# InterfacesA_CONNECTORS.net
KiCad netlist of a schematic drawn in Altium Designer
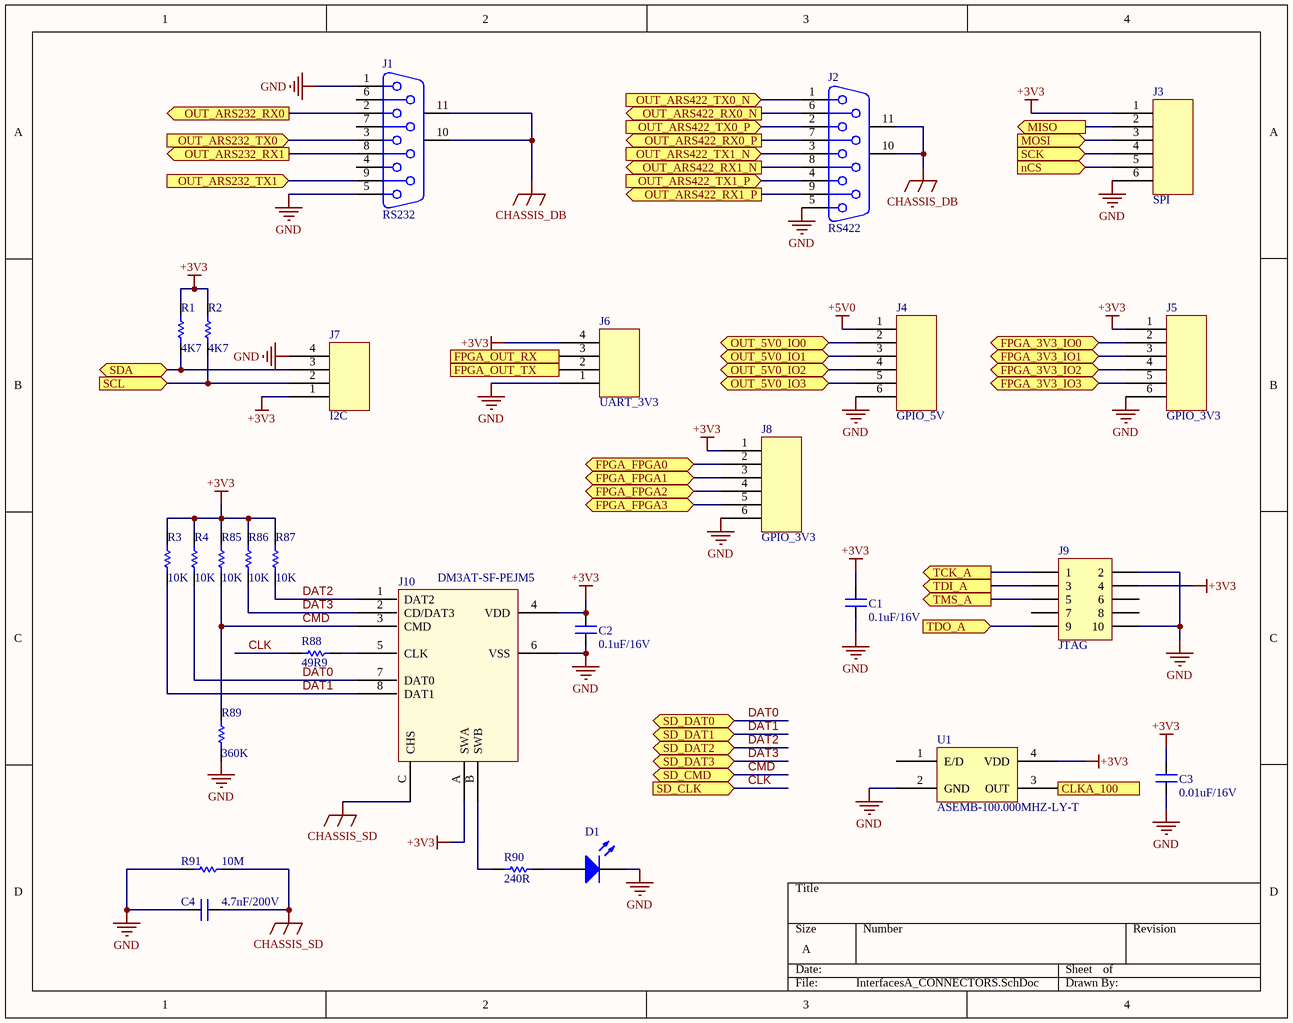
[diagram p0: InterfacesA_CONNECTORS.SchDoc]

(export (version "E")
  (design (tool "Eeschema 10.0.6"))
  (components
    (comp (ref "C1")
      (value "0.1uF/16V")
      (footprint "CAP_0805")
      (fields (field (name "Comment") "CAP_0805"))
      (libsource (lib "AdapterLib") (part "CAP_0805"))
    )
    (comp (ref "C2")
      (value "0.1uF/16V")
      (footprint "CAP_0805")
      (fields (field (name "Comment") "CAP_0805"))
      (libsource (lib "AdapterLib") (part "CAP_0805"))
    )
    (comp (ref "C3")
      (value "0.01uF/16V")
      (footprint "CAP_0805")
      (fields (field (name "Comment") "CAP_0805"))
      (libsource (lib "AdapterLib") (part "CAP_0805"))
    )
    (comp (ref "C4")
      (value "4.7nF/200V")
      (footprint "CAP_0805")
      (fields (field (name "Comment") "CAP_0805"))
      (libsource (lib "AdapterLib") (part "CAP_0805"))
    )
    (comp (ref "D1")
      (value "LED_0603")
      (footprint "LED_0603")
      (libsource (lib "AdapterLib") (part "LED_0603"))
    )
    (comp (ref "J1")
      (value "RS232")
      (footprint "D09S33E4GV00LF")
      (libsource (lib "AdapterLib") (part "D09S33E4GV00LF"))
    )
    (comp (ref "J2")
      (value "RS422")
      (footprint "D09S33E4GV00LF")
      (libsource (lib "AdapterLib") (part "D09S33E4GV00LF"))
    )
    (comp (ref "J3") (value "SPI") (footprint "HEADER_6") (libsource (lib "AdapterLib") (part "HEADER_6")))
    (comp (ref "J4")
      (value "GPIO_5V")
      (footprint "HEADER_6")
      (libsource (lib "AdapterLib") (part "HEADER_6"))
    )
    (comp (ref "J5")
      (value "GPIO_3V3")
      (footprint "HEADER_6")
      (libsource (lib "AdapterLib") (part "HEADER_6"))
    )
    (comp (ref "J6")
      (value "UART_3V3")
      (footprint "HEADER_4")
      (libsource (lib "AdapterLib") (part "HEADER_4"))
    )
    (comp (ref "J7") (value "I2C") (footprint "HEADER_4") (libsource (lib "AdapterLib") (part "HEADER_4")))
    (comp (ref "J8")
      (value "GPIO_3V3")
      (footprint "HEADER_6")
      (libsource (lib "AdapterLib") (part "HEADER_6"))
    )
    (comp (ref "J9")
      (value "JTAG")
      (footprint "HEADER 5x2")
      (description "Header, 5-Pin, Dual row")
      (fields (field (name "PUBLISHER") "Altium Limited"))
      (libsource (lib "AdapterLib") (part "Header 5X2"))
    )
    (comp (ref "J10")
      (value "DM3AT-SF-PEJM5")
      (footprint "DM3AT-SF-PEJM5")
      (description "CONN SM MicroSD")
      (libsource (lib "AdapterLib") (part "DM3AT-SF-PEJM5"))
    )
    (comp (ref "R1")
      (value "4K7")
      (footprint "RES_0805")
      (fields (field (name "Comment") "RES_0805"))
      (libsource (lib "AdapterLib") (part "RES_0805"))
    )
    (comp (ref "R2")
      (value "4K7")
      (footprint "RES_0805")
      (fields (field (name "Comment") "RES_0805"))
      (libsource (lib "AdapterLib") (part "RES_0805"))
    )
    (comp (ref "R3")
      (value "10K")
      (footprint "RES_0805")
      (fields (field (name "Comment") "RES_0805"))
      (libsource (lib "AdapterLib") (part "RES_0805"))
    )
    (comp (ref "R4")
      (value "10K")
      (footprint "RES_0805")
      (fields (field (name "Comment") "RES_0805"))
      (libsource (lib "AdapterLib") (part "RES_0805"))
    )
    (comp (ref "R85")
      (value "10K")
      (footprint "RES_0805")
      (fields (field (name "Comment") "RES_0805"))
      (libsource (lib "AdapterLib") (part "RES_0805"))
    )
    (comp (ref "R86")
      (value "10K")
      (footprint "RES_0805")
      (fields (field (name "Comment") "RES_0805"))
      (libsource (lib "AdapterLib") (part "RES_0805"))
    )
    (comp (ref "R87")
      (value "10K")
      (footprint "RES_0805")
      (fields (field (name "Comment") "RES_0805"))
      (libsource (lib "AdapterLib") (part "RES_0805"))
    )
    (comp (ref "R88")
      (value "49R9")
      (footprint "RES_0805")
      (fields (field (name "Comment") "RES_0805"))
      (libsource (lib "AdapterLib") (part "RES_0805"))
    )
    (comp (ref "R89")
      (value "360K")
      (footprint "RES_0805")
      (fields (field (name "Comment") "RES_0805"))
      (libsource (lib "AdapterLib") (part "RES_0805"))
    )
    (comp (ref "R90")
      (value "240R")
      (footprint "RES_0805")
      (fields (field (name "Comment") "RES_0805"))
      (libsource (lib "AdapterLib") (part "RES_0805"))
    )
    (comp (ref "R91")
      (value "10M")
      (footprint "RES_0805")
      (fields (field (name "Comment") "RES_0805"))
      (libsource (lib "AdapterLib") (part "RES_0805"))
    )
    (comp (ref "U1")
      (value "ASEMB-100.000MHZ-LY-T")
      (footprint "ASEMB-100.000MHZ-LY-T")
      (libsource (lib "AdapterLib") (part "ASEMB-100.000MHZ-LY-T"))
    )
  )
  (nets
    (net (code "1") (name "+3V3") (class "Default")
      (node (ref "C1") (pin "2") (pinfunction "2_2") (pintype "passive"))
      (node (ref "C2") (pin "2") (pinfunction "2_2") (pintype "passive"))
      (node (ref "C3") (pin "2") (pinfunction "2_2") (pintype "passive"))
      (node (ref "J10") (pin "4") (pinfunction "VDD_4") (pintype "passive"))
      (node (ref "J10") (pin "A") (pinfunction "SWA_A") (pintype "passive"))
      (node (ref "J3") (pin "1") (pintype "passive"))
      (node (ref "J5") (pin "1") (pintype "passive"))
      (node (ref "J6") (pin "4") (pintype "passive"))
      (node (ref "J7") (pin "1") (pintype "passive"))
      (node (ref "J8") (pin "1") (pintype "passive"))
      (node (ref "J9") (pin "4") (pinfunction "4_4") (pintype "passive"))
      (node (ref "R1") (pin "2") (pinfunction "2_2") (pintype "passive"))
      (node (ref "R2") (pin "2") (pinfunction "2_2") (pintype "passive"))
      (node (ref "R3") (pin "2") (pinfunction "2_2") (pintype "passive"))
      (node (ref "R4") (pin "2") (pinfunction "2_2") (pintype "passive"))
      (node (ref "R85") (pin "2") (pinfunction "2_2") (pintype "passive"))
      (node (ref "R86") (pin "2") (pinfunction "2_2") (pintype "passive"))
      (node (ref "R87") (pin "2") (pinfunction "2_2") (pintype "passive"))
      (node (ref "U1") (pin "4") (pinfunction "VDD_4") (pintype "passive"))
    )
    (net (code "2") (name "+5V0") (class "Default") (node (ref "J4") (pin "1") (pintype "passive")))
    (net (code "3") (name "/CLK") (class "Default")
      (node (ref "R88") (pin "2") (pinfunction "2_2") (pintype "passive"))
    )
    (net (code "4") (name "/CLKA_100") (class "Default")
      (node (ref "U1") (pin "3") (pinfunction "OUT_3") (pintype "passive"))
    )
    (net (code "5") (name "/CMD") (class "Default")
      (node (ref "J10") (pin "3") (pinfunction "CMD_3") (pintype "passive"))
      (node (ref "R85") (pin "1") (pinfunction "1_1") (pintype "passive"))
      (node (ref "R89") (pin "2") (pinfunction "2_2") (pintype "passive"))
    )
    (net (code "6") (name "/DAT0") (class "Default")
      (node (ref "J10") (pin "7") (pinfunction "DAT0_7") (pintype "passive"))
      (node (ref "R4") (pin "1") (pinfunction "1_1") (pintype "passive"))
    )
    (net (code "7") (name "/DAT1") (class "Default")
      (node (ref "J10") (pin "8") (pinfunction "DAT1_8") (pintype "passive"))
      (node (ref "R3") (pin "1") (pinfunction "1_1") (pintype "passive"))
    )
    (net (code "8") (name "/DAT2") (class "Default")
      (node (ref "J10") (pin "1") (pinfunction "DAT2_1") (pintype "passive"))
      (node (ref "R87") (pin "1") (pinfunction "1_1") (pintype "passive"))
    )
    (net (code "9") (name "/DAT3") (class "Default")
      (node (ref "J10") (pin "2") (pinfunction "CD/DAT3_2") (pintype "passive"))
      (node (ref "R86") (pin "1") (pinfunction "1_1") (pintype "passive"))
    )
    (net (code "10") (name "/FPGA_3V3_IO0") (class "Default") (node (ref "J5") (pin "2") (pintype "passive")))
    (net (code "11") (name "/FPGA_3V3_IO1") (class "Default") (node (ref "J5") (pin "3") (pintype "passive")))
    (net (code "12") (name "/FPGA_3V3_IO2") (class "Default") (node (ref "J5") (pin "4") (pintype "passive")))
    (net (code "13") (name "/FPGA_3V3_IO3") (class "Default") (node (ref "J5") (pin "5") (pintype "passive")))
    (net (code "14") (name "/FPGA_FPGA0") (class "Default") (node (ref "J8") (pin "2") (pintype "passive")))
    (net (code "15") (name "/FPGA_FPGA1") (class "Default") (node (ref "J8") (pin "3") (pintype "passive")))
    (net (code "16") (name "/FPGA_FPGA2") (class "Default") (node (ref "J8") (pin "4") (pintype "passive")))
    (net (code "17") (name "/FPGA_FPGA3") (class "Default") (node (ref "J8") (pin "5") (pintype "passive")))
    (net (code "18") (name "/FPGA_OUT_RX") (class "Default") (node (ref "J6") (pin "3") (pintype "passive")))
    (net (code "19") (name "/FPGA_OUT_TX") (class "Default") (node (ref "J6") (pin "2") (pintype "passive")))
    (net (code "20") (name "/MISO") (class "Default") (node (ref "J3") (pin "2") (pintype "passive")))
    (net (code "21") (name "/MOSI") (class "Default") (node (ref "J3") (pin "3") (pintype "passive")))
    (net (code "22") (name "/OUT_5V0_IO0") (class "Default") (node (ref "J4") (pin "2") (pintype "passive")))
    (net (code "23") (name "/OUT_5V0_IO1") (class "Default") (node (ref "J4") (pin "3") (pintype "passive")))
    (net (code "24") (name "/OUT_5V0_IO2") (class "Default") (node (ref "J4") (pin "4") (pintype "passive")))
    (net (code "25") (name "/OUT_5V0_IO3") (class "Default") (node (ref "J4") (pin "5") (pintype "passive")))
    (net (code "26") (name "/OUT_ARS232_RX0") (class "Default")
      (node (ref "J1") (pin "2") (pinfunction "2_2") (pintype "passive"))
    )
    (net (code "27") (name "/OUT_ARS232_RX1") (class "Default")
      (node (ref "J1") (pin "8") (pinfunction "8_8") (pintype "passive"))
    )
    (net (code "28") (name "/OUT_ARS232_TX0") (class "Default")
      (node (ref "J1") (pin "3") (pinfunction "3_3") (pintype "passive"))
    )
    (net (code "29") (name "/OUT_ARS232_TX1") (class "Default")
      (node (ref "J1") (pin "9") (pinfunction "9_9") (pintype "passive"))
    )
    (net (code "30") (name "/OUT_ARS422_RX0_N") (class "Default")
      (node (ref "J2") (pin "6") (pinfunction "6_6") (pintype "passive"))
    )
    (net (code "31") (name "/OUT_ARS422_RX0_P") (class "Default")
      (node (ref "J2") (pin "7") (pinfunction "7_7") (pintype "passive"))
    )
    (net (code "32") (name "/OUT_ARS422_RX1_N") (class "Default")
      (node (ref "J2") (pin "8") (pinfunction "8_8") (pintype "passive"))
    )
    (net (code "33") (name "/OUT_ARS422_RX1_P") (class "Default")
      (node (ref "J2") (pin "9") (pinfunction "9_9") (pintype "passive"))
    )
    (net (code "34") (name "/OUT_ARS422_TX0_N") (class "Default")
      (node (ref "J2") (pin "1") (pinfunction "1_1") (pintype "passive"))
    )
    (net (code "35") (name "/OUT_ARS422_TX0_P") (class "Default")
      (node (ref "J2") (pin "2") (pinfunction "2_2") (pintype "passive"))
    )
    (net (code "36") (name "/OUT_ARS422_TX1_N") (class "Default")
      (node (ref "J2") (pin "3") (pinfunction "3_3") (pintype "passive"))
    )
    (net (code "37") (name "/OUT_ARS422_TX1_P") (class "Default")
      (node (ref "J2") (pin "4") (pinfunction "4_4") (pintype "passive"))
    )
    (net (code "38") (name "/SCK") (class "Default") (node (ref "J3") (pin "4") (pintype "passive")))
    (net (code "39") (name "/SCL") (class "Default")
      (node (ref "J7") (pin "2") (pintype "passive"))
      (node (ref "R2") (pin "1") (pinfunction "1_1") (pintype "passive"))
    )
    (net (code "40") (name "/SDA") (class "Default")
      (node (ref "J7") (pin "3") (pintype "passive"))
      (node (ref "R1") (pin "1") (pinfunction "1_1") (pintype "passive"))
    )
    (net (code "41") (name "/TCK_A") (class "Default")
      (node (ref "J9") (pin "1") (pinfunction "1_1") (pintype "passive"))
    )
    (net (code "42") (name "/TDI_A") (class "Default")
      (node (ref "J9") (pin "3") (pinfunction "3_3") (pintype "passive"))
    )
    (net (code "43") (name "/TDO_A") (class "Default")
      (node (ref "J9") (pin "9") (pinfunction "9_9") (pintype "passive"))
    )
    (net (code "44") (name "/TMS_A") (class "Default")
      (node (ref "J9") (pin "5") (pinfunction "5_5") (pintype "passive"))
    )
    (net (code "45") (name "/nCS") (class "Default") (node (ref "J3") (pin "5") (pintype "passive")))
    (net (code "46") (name "CHASSIS_DB") (class "Default")
      (node (ref "J1") (pin "10") (pinfunction "MH1_10") (pintype "passive"))
      (node (ref "J1") (pin "11") (pinfunction "MH2_11") (pintype "passive"))
      (node (ref "J2") (pin "10") (pinfunction "MH1_10") (pintype "passive"))
      (node (ref "J2") (pin "11") (pinfunction "MH2_11") (pintype "passive"))
    )
    (net (code "47") (name "CHASSIS_SD") (class "Default")
      (node (ref "C4") (pin "1") (pinfunction "1_1") (pintype "passive"))
      (node (ref "J10") (pin "C") (pinfunction "CHS_C") (pintype "passive"))
      (node (ref "R91") (pin "1") (pinfunction "1_1") (pintype "passive"))
    )
    (net (code "48") (name "GND") (class "Default")
      (node (ref "C1") (pin "1") (pinfunction "1_1") (pintype "passive"))
      (node (ref "C2") (pin "1") (pinfunction "1_1") (pintype "passive"))
      (node (ref "C3") (pin "1") (pinfunction "1_1") (pintype "passive"))
      (node (ref "C4") (pin "2") (pinfunction "2_2") (pintype "passive"))
      (node (ref "D1") (pin "2") (pinfunction "K_2") (pintype "passive"))
      (node (ref "J1") (pin "1") (pinfunction "1_1") (pintype "passive"))
      (node (ref "J1") (pin "5") (pinfunction "5_5") (pintype "passive"))
      (node (ref "J10") (pin "6") (pinfunction "VSS_6") (pintype "passive"))
      (node (ref "J2") (pin "5") (pinfunction "5_5") (pintype "passive"))
      (node (ref "J3") (pin "6") (pintype "passive"))
      (node (ref "J4") (pin "6") (pintype "passive"))
      (node (ref "J5") (pin "6") (pintype "passive"))
      (node (ref "J6") (pin "1") (pintype "passive"))
      (node (ref "J7") (pin "4") (pintype "passive"))
      (node (ref "J8") (pin "6") (pintype "passive"))
      (node (ref "J9") (pin "10") (pinfunction "10_10") (pintype "passive"))
      (node (ref "J9") (pin "2") (pinfunction "2_2") (pintype "passive"))
      (node (ref "R89") (pin "1") (pinfunction "1_1") (pintype "passive"))
      (node (ref "R91") (pin "2") (pinfunction "2_2") (pintype "passive"))
      (node (ref "U1") (pin "2") (pinfunction "GND_2") (pintype "passive"))
    )
    (net (code "49") (name "Net-(D1-A)") (class "Default")
      (node (ref "D1") (pin "1") (pinfunction "A_1") (pintype "passive"))
      (node (ref "R90") (pin "1") (pinfunction "1_1") (pintype "passive"))
    )
    (net (code "50") (name "Net-(J10-CLK)") (class "Default")
      (node (ref "J10") (pin "5") (pinfunction "CLK_5") (pintype "passive"))
      (node (ref "R88") (pin "1") (pinfunction "1_1") (pintype "passive"))
    )
    (net (code "51") (name "Net-(J10-SWB)") (class "Default")
      (node (ref "J10") (pin "B") (pinfunction "SWB_B") (pintype "passive"))
      (node (ref "R90") (pin "2") (pinfunction "2_2") (pintype "passive"))
    )
    (net (code "52") (name "unconnected-(J1-Pad4)") (class "Default")
      (node (ref "J1") (pin "4") (pinfunction "4_4") (pintype "passive"))
    )
    (net (code "53") (name "unconnected-(J1-Pad6)") (class "Default")
      (node (ref "J1") (pin "6") (pinfunction "6_6") (pintype "passive"))
    )
    (net (code "54") (name "unconnected-(J1-Pad7)") (class "Default")
      (node (ref "J1") (pin "7") (pinfunction "7_7") (pintype "passive"))
    )
    (net (code "55") (name "unconnected-(J9-Pad6)") (class "Default")
      (node (ref "J9") (pin "6") (pinfunction "6_6") (pintype "passive"))
    )
    (net (code "56") (name "unconnected-(J9-Pad7)") (class "Default")
      (node (ref "J9") (pin "7") (pinfunction "7_7") (pintype "passive"))
    )
    (net (code "57") (name "unconnected-(J9-Pad8)") (class "Default")
      (node (ref "J9") (pin "8") (pinfunction "8_8") (pintype "passive"))
    )
    (net (code "58") (name "unconnected-(U1-E{slash}D-Pad1)") (class "Default")
      (node (ref "U1") (pin "1") (pinfunction "E/D_1") (pintype "passive"))
    )
  )
)
